# pre_autoRoute.net
KiCad netlist of a schematic drawn in EAGLE
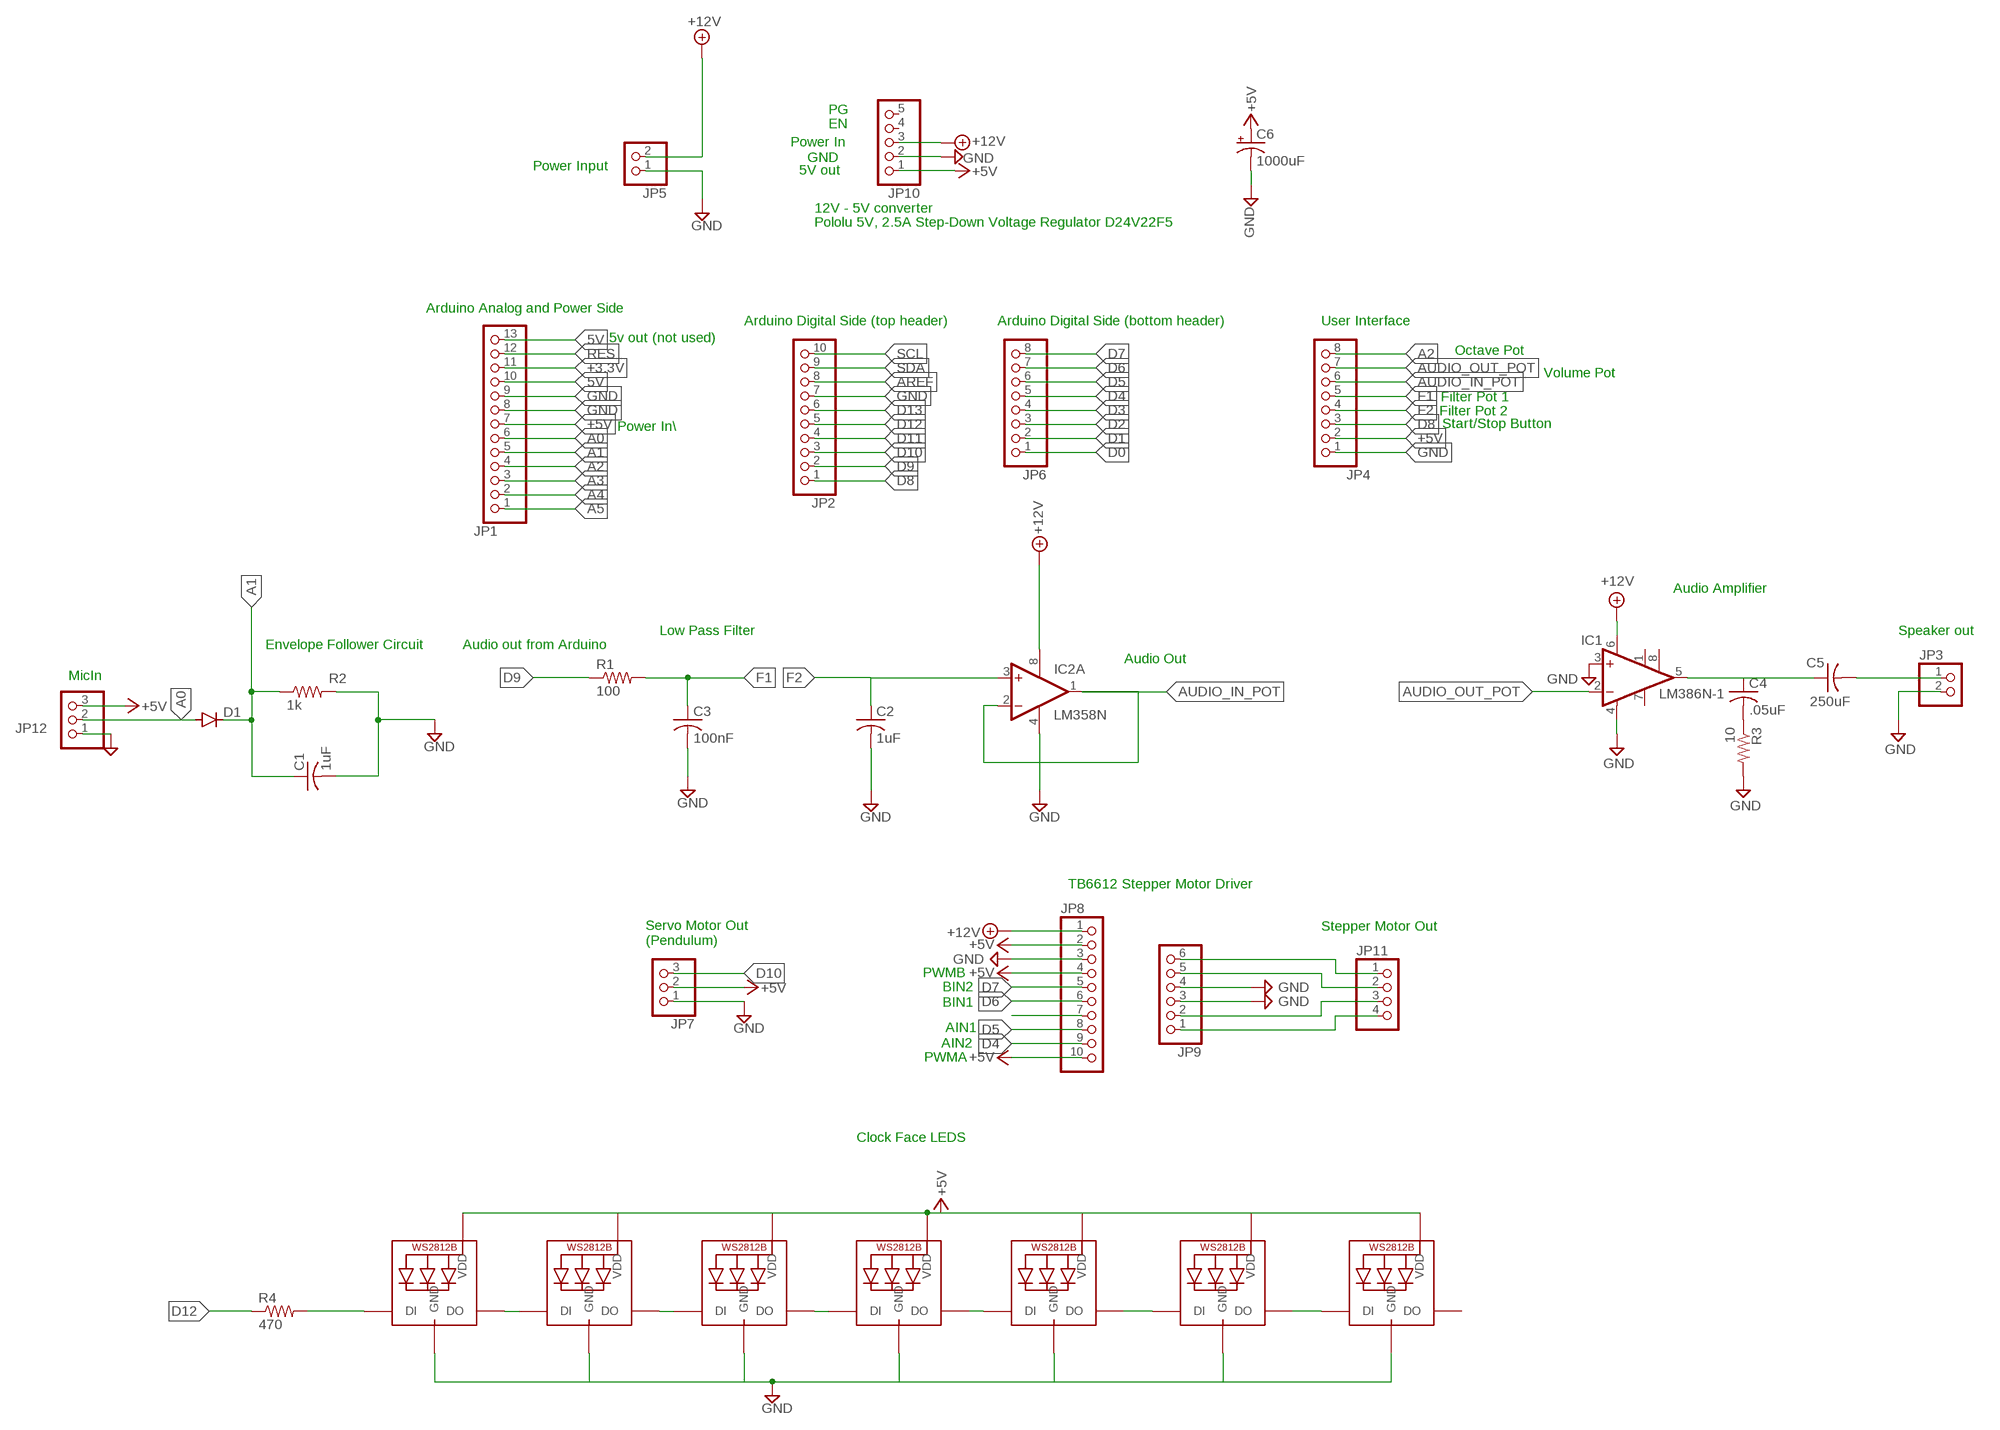
[diagram p0: schematic, sheet 1]

(export (version "E")
  (design (tool "Eeschema 10.0.6"))
  (components
    (comp (ref "C1")
      (value "1uF")
      (footprint "eagle-import:C025-050X050")
      (libsource (lib "eagle-import") (part "C-US025-050X050"))
    )
    (comp (ref "C2")
      (value "1uF")
      (footprint "eagle-import:C025-040X050")
      (libsource (lib "eagle-import") (part "C-US025-040X050"))
    )
    (comp (ref "C3")
      (value "100nF")
      (footprint "eagle-import:C025-040X050")
      (libsource (lib "eagle-import") (part "C-US025-040X050"))
    )
    (comp (ref "C4")
      (value ".05uF")
      (footprint "eagle-import:C025-040X050")
      (libsource (lib "eagle-import") (part "C-US025-040X050"))
    )
    (comp (ref "C5")
      (value "250uF")
      (footprint "eagle-import:C025-040X050")
      (libsource (lib "eagle-import") (part "C-US025-040X050"))
    )
    (comp (ref "C6")
      (value "1000uF")
      (footprint "eagle-import:E5-8,5")
      (libsource (lib "eagle-import") (part "CPOL-USE5-8.5"))
    )
    (comp (ref "D1")
      (value "1N4148DO35-7")
      (footprint "eagle-import:DO35-7")
      (libsource (lib "eagle-import") (part "1N4148DO35-7"))
    )
    (comp (ref "IC1")
      (value "LM386N-1")
      (footprint "eagle-import:DIL08")
      (libsource (lib "eagle-import") (part "LM386?-N1"))
    )
    (comp (ref "IC2")
      (value "LM358N")
      (footprint "eagle-import:DIL08")
      (libsource (lib "eagle-import") (part "LM358N"))
    )
    (comp (ref "JP1")
      (value "PINHD-1X13")
      (footprint "eagle-import:1X13")
      (libsource (lib "eagle-import") (part "PINHD-1X13"))
    )
    (comp (ref "JP2")
      (value "PINHD-1X10")
      (footprint "eagle-import:1X10")
      (libsource (lib "eagle-import") (part "PINHD-1X10"))
    )
    (comp (ref "JP3")
      (value "PINHD-1X2")
      (footprint "eagle-import:1X02")
      (libsource (lib "eagle-import") (part "PINHD-1X2"))
    )
    (comp (ref "JP4")
      (value "PINHD-1X8")
      (footprint "eagle-import:1X08")
      (libsource (lib "eagle-import") (part "PINHD-1X8"))
    )
    (comp (ref "JP5")
      (value "PINHD-1X2")
      (footprint "eagle-import:1X02")
      (libsource (lib "eagle-import") (part "PINHD-1X2"))
    )
    (comp (ref "JP6")
      (value "PINHD-1X8")
      (footprint "eagle-import:1X08")
      (libsource (lib "eagle-import") (part "PINHD-1X8"))
    )
    (comp (ref "JP7")
      (value "PINHD-1X3")
      (footprint "eagle-import:1X03")
      (libsource (lib "eagle-import") (part "PINHD-1X3"))
    )
    (comp (ref "JP8")
      (value "PINHD-1X10")
      (footprint "eagle-import:1X10")
      (libsource (lib "eagle-import") (part "PINHD-1X10"))
    )
    (comp (ref "JP9")
      (value "PINHD-1X6")
      (footprint "eagle-import:1X06")
      (libsource (lib "eagle-import") (part "PINHD-1X6"))
    )
    (comp (ref "JP10")
      (value "PINHD-1X5")
      (footprint "eagle-import:1X05")
      (libsource (lib "eagle-import") (part "PINHD-1X5"))
    )
    (comp (ref "JP11")
      (value "PINHD-1X4")
      (footprint "eagle-import:1X04")
      (libsource (lib "eagle-import") (part "PINHD-1X4"))
    )
    (comp (ref "JP12")
      (value "PINHD-1X3")
      (footprint "eagle-import:1X03")
      (libsource (lib "eagle-import") (part "PINHD-1X3"))
    )
    (comp (ref "LED2")
      (value "WS2812B_5050N")
      (footprint "eagle-import:WS2812B-NARROW")
      (libsource (lib "eagle-import") (part "WS2812B_5050N"))
    )
    (comp (ref "LED3")
      (value "WS2812B_5050N")
      (footprint "eagle-import:WS2812B-NARROW")
      (libsource (lib "eagle-import") (part "WS2812B_5050N"))
    )
    (comp (ref "LED4")
      (value "WS2812B_5050N")
      (footprint "eagle-import:WS2812B-NARROW")
      (libsource (lib "eagle-import") (part "WS2812B_5050N"))
    )
    (comp (ref "LED5")
      (value "WS2812B_5050N")
      (footprint "eagle-import:WS2812B-NARROW")
      (libsource (lib "eagle-import") (part "WS2812B_5050N"))
    )
    (comp (ref "LED6")
      (value "WS2812B_5050N")
      (footprint "eagle-import:WS2812B-NARROW")
      (libsource (lib "eagle-import") (part "WS2812B_5050N"))
    )
    (comp (ref "LED7")
      (value "WS2812B_5050N")
      (footprint "eagle-import:WS2812B-NARROW")
      (libsource (lib "eagle-import") (part "WS2812B_5050N"))
    )
    (comp (ref "LED8")
      (value "WS2812B_5050N")
      (footprint "eagle-import:WS2812B-NARROW")
      (libsource (lib "eagle-import") (part "WS2812B_5050N"))
    )
    (comp (ref "R1")
      (value "100")
      (footprint "eagle-import:0204_7")
      (libsource (lib "eagle-import") (part "R-US_0204/7"))
    )
    (comp (ref "R2")
      (value "1k")
      (footprint "eagle-import:0204_7")
      (libsource (lib "eagle-import") (part "R-US_0204/7"))
    )
    (comp (ref "R3")
      (value "10")
      (footprint "eagle-import:0204_7")
      (libsource (lib "eagle-import") (part "R-US_0204/7"))
    )
    (comp (ref "R4")
      (value "470")
      (footprint "eagle-import:0204_7")
      (libsource (lib "eagle-import") (part "R-US_0204/7"))
    )
  )
  (nets
    (net (code "1") (name "+3.3V") (class "Default")
      (node (ref "JP1") (pin "11") (pinfunction "11_11") (pintype "passive"))
    )
    (net (code "2") (name "+5V") (class "Default")
      (node (ref "C6") (pin "+") (pinfunction "+_+") (pintype "passive"))
      (node (ref "JP1") (pin "7") (pinfunction "7_7") (pintype "passive"))
      (node (ref "JP10") (pin "1") (pinfunction "1_1") (pintype "passive"))
      (node (ref "JP12") (pin "3") (pinfunction "3_3") (pintype "passive"))
      (node (ref "JP4") (pin "2") (pinfunction "2_2") (pintype "passive"))
      (node (ref "JP7") (pin "2") (pinfunction "2_2") (pintype "passive"))
      (node (ref "JP8") (pin "10") (pinfunction "10_10") (pintype "passive"))
      (node (ref "JP8") (pin "2") (pinfunction "2_2") (pintype "passive"))
      (node (ref "JP8") (pin "4") (pinfunction "4_4") (pintype "passive"))
      (node (ref "LED2") (pin "1-VDD") (pinfunction "VDD_1-VDD") (pintype "power_in"))
      (node (ref "LED3") (pin "1-VDD") (pinfunction "VDD_1-VDD") (pintype "power_in"))
      (node (ref "LED4") (pin "1-VDD") (pinfunction "VDD_1-VDD") (pintype "power_in"))
      (node (ref "LED5") (pin "1-VDD") (pinfunction "VDD_1-VDD") (pintype "power_in"))
      (node (ref "LED6") (pin "1-VDD") (pinfunction "VDD_1-VDD") (pintype "power_in"))
      (node (ref "LED7") (pin "1-VDD") (pinfunction "VDD_1-VDD") (pintype "power_in"))
      (node (ref "LED8") (pin "1-VDD") (pinfunction "VDD_1-VDD") (pintype "power_in"))
    )
    (net (code "3") (name "+12V") (class "Default")
      (node (ref "IC1") (pin "6") (pinfunction "VS_6") (pintype "power_in"))
      (node (ref "IC2") (pin "8") (pinfunction "V+_8") (pintype "power_in"))
      (node (ref "JP10") (pin "3") (pinfunction "3_3") (pintype "passive"))
      (node (ref "JP5") (pin "2") (pinfunction "2_2") (pintype "passive"))
      (node (ref "JP8") (pin "1") (pinfunction "1_1") (pintype "passive"))
    )
    (net (code "4") (name "5V") (class "Default")
      (node (ref "JP1") (pin "10") (pinfunction "10_10") (pintype "passive"))
      (node (ref "JP1") (pin "13") (pinfunction "13_13") (pintype "passive"))
    )
    (net (code "5") (name "A0") (class "Default")
      (node (ref "D1") (pin "A") (pinfunction "A_A") (pintype "passive"))
      (node (ref "JP1") (pin "6") (pinfunction "6_6") (pintype "passive"))
      (node (ref "JP12") (pin "2") (pinfunction "2_2") (pintype "passive"))
    )
    (net (code "6") (name "A1") (class "Default")
      (node (ref "C1") (pin "1") (pinfunction "1_1") (pintype "passive"))
      (node (ref "D1") (pin "C") (pinfunction "C_C") (pintype "passive"))
      (node (ref "JP1") (pin "5") (pinfunction "5_5") (pintype "passive"))
      (node (ref "R2") (pin "1") (pinfunction "1_1") (pintype "passive"))
    )
    (net (code "7") (name "A2") (class "Default")
      (node (ref "JP1") (pin "4") (pinfunction "4_4") (pintype "passive"))
      (node (ref "JP4") (pin "8") (pinfunction "8_8") (pintype "passive"))
    )
    (net (code "8") (name "A3") (class "Default")
      (node (ref "JP1") (pin "3") (pinfunction "3_3") (pintype "passive"))
    )
    (net (code "9") (name "A4") (class "Default")
      (node (ref "JP1") (pin "2") (pinfunction "2_2") (pintype "passive"))
    )
    (net (code "10") (name "A5") (class "Default")
      (node (ref "JP1") (pin "1") (pinfunction "1_1") (pintype "passive"))
    )
    (net (code "11") (name "AREF") (class "Default")
      (node (ref "JP2") (pin "8") (pinfunction "8_8") (pintype "passive"))
    )
    (net (code "12") (name "AUDIO_IN_POT") (class "Default")
      (node (ref "IC2") (pin "1") (pinfunction "OUT_1") (pintype "output"))
      (node (ref "IC2") (pin "2") (pinfunction "-IN_2") (pintype "input"))
      (node (ref "JP4") (pin "6") (pinfunction "6_6") (pintype "passive"))
    )
    (net (code "13") (name "AUDIO_OUT_POT") (class "Default")
      (node (ref "IC1") (pin "2") (pinfunction "-IN_2") (pintype "input"))
      (node (ref "JP4") (pin "7") (pinfunction "7_7") (pintype "passive"))
    )
    (net (code "14") (name "D0") (class "Default")
      (node (ref "JP6") (pin "1") (pinfunction "1_1") (pintype "passive"))
    )
    (net (code "15") (name "D1") (class "Default")
      (node (ref "JP6") (pin "2") (pinfunction "2_2") (pintype "passive"))
    )
    (net (code "16") (name "D2") (class "Default")
      (node (ref "JP6") (pin "3") (pinfunction "3_3") (pintype "passive"))
    )
    (net (code "17") (name "D3") (class "Default")
      (node (ref "JP6") (pin "4") (pinfunction "4_4") (pintype "passive"))
    )
    (net (code "18") (name "D4") (class "Default")
      (node (ref "JP6") (pin "5") (pinfunction "5_5") (pintype "passive"))
      (node (ref "JP8") (pin "9") (pinfunction "9_9") (pintype "passive"))
    )
    (net (code "19") (name "D5") (class "Default")
      (node (ref "JP6") (pin "6") (pinfunction "6_6") (pintype "passive"))
      (node (ref "JP8") (pin "8") (pinfunction "8_8") (pintype "passive"))
    )
    (net (code "20") (name "D6") (class "Default")
      (node (ref "JP6") (pin "7") (pinfunction "7_7") (pintype "passive"))
      (node (ref "JP8") (pin "6") (pinfunction "6_6") (pintype "passive"))
    )
    (net (code "21") (name "D7") (class "Default")
      (node (ref "JP6") (pin "8") (pinfunction "8_8") (pintype "passive"))
      (node (ref "JP8") (pin "5") (pinfunction "5_5") (pintype "passive"))
    )
    (net (code "22") (name "D8") (class "Default")
      (node (ref "JP2") (pin "1") (pinfunction "1_1") (pintype "passive"))
      (node (ref "JP4") (pin "3") (pinfunction "3_3") (pintype "passive"))
    )
    (net (code "23") (name "D9") (class "Default")
      (node (ref "JP2") (pin "2") (pinfunction "2_2") (pintype "passive"))
      (node (ref "R1") (pin "1") (pinfunction "1_1") (pintype "passive"))
    )
    (net (code "24") (name "D10") (class "Default")
      (node (ref "JP2") (pin "3") (pinfunction "3_3") (pintype "passive"))
      (node (ref "JP7") (pin "3") (pinfunction "3_3") (pintype "passive"))
    )
    (net (code "25") (name "D11") (class "Default")
      (node (ref "JP2") (pin "4") (pinfunction "4_4") (pintype "passive"))
    )
    (net (code "26") (name "D12") (class "Default")
      (node (ref "JP2") (pin "5") (pinfunction "5_5") (pintype "passive"))
      (node (ref "R4") (pin "1") (pinfunction "1_1") (pintype "passive"))
    )
    (net (code "27") (name "D13") (class "Default")
      (node (ref "JP2") (pin "6") (pinfunction "6_6") (pintype "passive"))
    )
    (net (code "28") (name "F1") (class "Default")
      (node (ref "C3") (pin "1") (pinfunction "1_1") (pintype "passive"))
      (node (ref "JP4") (pin "5") (pinfunction "5_5") (pintype "passive"))
      (node (ref "R1") (pin "2") (pinfunction "2_2") (pintype "passive"))
    )
    (net (code "29") (name "F2") (class "Default")
      (node (ref "C2") (pin "1") (pinfunction "1_1") (pintype "passive"))
      (node (ref "IC2") (pin "3") (pinfunction "+IN_3") (pintype "input"))
      (node (ref "JP4") (pin "4") (pinfunction "4_4") (pintype "passive"))
    )
    (net (code "30") (name "GND") (class "Default")
      (node (ref "C1") (pin "2") (pinfunction "2_2") (pintype "passive"))
      (node (ref "C2") (pin "2") (pinfunction "2_2") (pintype "passive"))
      (node (ref "C3") (pin "2") (pinfunction "2_2") (pintype "passive"))
      (node (ref "C6") (pin "-") (pinfunction "-_-") (pintype "passive"))
      (node (ref "IC1") (pin "3") (pinfunction "+IN_3") (pintype "input"))
      (node (ref "IC1") (pin "4") (pinfunction "GND_4") (pintype "power_in"))
      (node (ref "IC2") (pin "4") (pinfunction "V-_4") (pintype "power_in"))
      (node (ref "JP1") (pin "8") (pinfunction "8_8") (pintype "passive"))
      (node (ref "JP1") (pin "9") (pinfunction "9_9") (pintype "passive"))
      (node (ref "JP10") (pin "2") (pinfunction "2_2") (pintype "passive"))
      (node (ref "JP12") (pin "1") (pinfunction "1_1") (pintype "passive"))
      (node (ref "JP2") (pin "7") (pinfunction "7_7") (pintype "passive"))
      (node (ref "JP3") (pin "2") (pinfunction "2_2") (pintype "passive"))
      (node (ref "JP4") (pin "1") (pinfunction "1_1") (pintype "passive"))
      (node (ref "JP5") (pin "1") (pinfunction "1_1") (pintype "passive"))
      (node (ref "JP7") (pin "1") (pinfunction "1_1") (pintype "passive"))
      (node (ref "JP8") (pin "3") (pinfunction "3_3") (pintype "passive"))
      (node (ref "JP9") (pin "3") (pinfunction "3_3") (pintype "passive"))
      (node (ref "JP9") (pin "4") (pinfunction "4_4") (pintype "passive"))
      (node (ref "LED2") (pin "3-GND") (pinfunction "GND_3-GND") (pintype "power_in"))
      (node (ref "LED3") (pin "3-GND") (pinfunction "GND_3-GND") (pintype "power_in"))
      (node (ref "LED4") (pin "3-GND") (pinfunction "GND_3-GND") (pintype "power_in"))
      (node (ref "LED5") (pin "3-GND") (pinfunction "GND_3-GND") (pintype "power_in"))
      (node (ref "LED6") (pin "3-GND") (pinfunction "GND_3-GND") (pintype "power_in"))
      (node (ref "LED7") (pin "3-GND") (pinfunction "GND_3-GND") (pintype "power_in"))
      (node (ref "LED8") (pin "3-GND") (pinfunction "GND_3-GND") (pintype "power_in"))
      (node (ref "R2") (pin "2") (pinfunction "2_2") (pintype "passive"))
      (node (ref "R3") (pin "2") (pinfunction "2_2") (pintype "passive"))
    )
    (net (code "31") (name "Net-(C4-Pad2)") (class "Default")
      (node (ref "C4") (pin "2") (pinfunction "2_2") (pintype "passive"))
      (node (ref "R3") (pin "1") (pinfunction "1_1") (pintype "passive"))
    )
    (net (code "32") (name "Net-(C5-Pad2)") (class "Default")
      (node (ref "C5") (pin "2") (pinfunction "2_2") (pintype "passive"))
      (node (ref "JP3") (pin "1") (pinfunction "1_1") (pintype "passive"))
    )
    (net (code "33") (name "Net-(IC1-OUT)") (class "Default")
      (node (ref "C4") (pin "1") (pinfunction "1_1") (pintype "passive"))
      (node (ref "C5") (pin "1") (pinfunction "1_1") (pintype "passive"))
      (node (ref "IC1") (pin "5") (pinfunction "OUT_5") (pintype "output"))
    )
    (net (code "34") (name "Net-(JP11-Pad1)") (class "Default")
      (node (ref "JP11") (pin "1") (pinfunction "1_1") (pintype "passive"))
      (node (ref "JP9") (pin "6") (pinfunction "6_6") (pintype "passive"))
    )
    (net (code "35") (name "Net-(JP11-Pad2)") (class "Default")
      (node (ref "JP11") (pin "2") (pinfunction "2_2") (pintype "passive"))
      (node (ref "JP9") (pin "5") (pinfunction "5_5") (pintype "passive"))
    )
    (net (code "36") (name "Net-(JP11-Pad3)") (class "Default")
      (node (ref "JP11") (pin "3") (pinfunction "3_3") (pintype "passive"))
      (node (ref "JP9") (pin "2") (pinfunction "2_2") (pintype "passive"))
    )
    (net (code "37") (name "Net-(JP11-Pad4)") (class "Default")
      (node (ref "JP11") (pin "4") (pinfunction "4_4") (pintype "passive"))
      (node (ref "JP9") (pin "1") (pinfunction "1_1") (pintype "passive"))
    )
    (net (code "38") (name "Net-(LED2-DI)") (class "Default")
      (node (ref "LED2") (pin "4-DIN") (pinfunction "DI_4-DIN") (pintype "input"))
      (node (ref "R4") (pin "2") (pinfunction "2_2") (pintype "passive"))
    )
    (net (code "39") (name "Net-(LED2-DO)") (class "Default")
      (node (ref "LED2") (pin "2-DOUT") (pinfunction "DO_2-DOUT") (pintype "output"))
      (node (ref "LED3") (pin "4-DIN") (pinfunction "DI_4-DIN") (pintype "input"))
    )
    (net (code "40") (name "Net-(LED3-DO)") (class "Default")
      (node (ref "LED3") (pin "2-DOUT") (pinfunction "DO_2-DOUT") (pintype "output"))
      (node (ref "LED4") (pin "4-DIN") (pinfunction "DI_4-DIN") (pintype "input"))
    )
    (net (code "41") (name "Net-(LED4-DO)") (class "Default")
      (node (ref "LED4") (pin "2-DOUT") (pinfunction "DO_2-DOUT") (pintype "output"))
      (node (ref "LED5") (pin "4-DIN") (pinfunction "DI_4-DIN") (pintype "input"))
    )
    (net (code "42") (name "Net-(LED5-DO)") (class "Default")
      (node (ref "LED5") (pin "2-DOUT") (pinfunction "DO_2-DOUT") (pintype "output"))
      (node (ref "LED6") (pin "4-DIN") (pinfunction "DI_4-DIN") (pintype "input"))
    )
    (net (code "43") (name "Net-(LED6-DO)") (class "Default")
      (node (ref "LED6") (pin "2-DOUT") (pinfunction "DO_2-DOUT") (pintype "output"))
      (node (ref "LED7") (pin "4-DIN") (pinfunction "DI_4-DIN") (pintype "input"))
    )
    (net (code "44") (name "Net-(LED7-DO)") (class "Default")
      (node (ref "LED7") (pin "2-DOUT") (pinfunction "DO_2-DOUT") (pintype "output"))
      (node (ref "LED8") (pin "4-DIN") (pinfunction "DI_4-DIN") (pintype "input"))
    )
    (net (code "45") (name "RES") (class "Default")
      (node (ref "JP1") (pin "12") (pinfunction "12_12") (pintype "passive"))
    )
    (net (code "46") (name "SCL") (class "Default")
      (node (ref "JP2") (pin "10") (pinfunction "10_10") (pintype "passive"))
    )
    (net (code "47") (name "SDA") (class "Default")
      (node (ref "JP2") (pin "9") (pinfunction "9_9") (pintype "passive"))
    )
    (net (code "48") (name "unconnected-(IC1-BYPASS-Pad7)") (class "Default")
      (node (ref "IC1") (pin "7") (pinfunction "BYPASS_7") (pintype "passive"))
    )
    (net (code "49") (name "unconnected-(IC1-GAIN-Pad1)") (class "Default")
      (node (ref "IC1") (pin "1") (pinfunction "GAIN_1") (pintype "passive"))
    )
    (net (code "50") (name "unconnected-(IC1-GAIN-Pad8)") (class "Default")
      (node (ref "IC1") (pin "8") (pinfunction "GAIN_8") (pintype "passive"))
    )
    (net (code "51") (name "unconnected-(JP8-Pad7)") (class "Default")
      (node (ref "JP8") (pin "7") (pinfunction "7_7") (pintype "passive"))
    )
    (net (code "52") (name "unconnected-(JP10-Pad4)") (class "Default")
      (node (ref "JP10") (pin "4") (pinfunction "4_4") (pintype "passive"))
    )
    (net (code "53") (name "unconnected-(JP10-Pad5)") (class "Default")
      (node (ref "JP10") (pin "5") (pinfunction "5_5") (pintype "passive"))
    )
    (net (code "54") (name "unconnected-(LED8-DO-Pad2-DOUT)") (class "Default")
      (node (ref "LED8") (pin "2-DOUT") (pinfunction "DO_2-DOUT") (pintype "output"))
    )
  )
)
